# jms578.net
KiCad netlist of a schematic drawn in Altium Designer
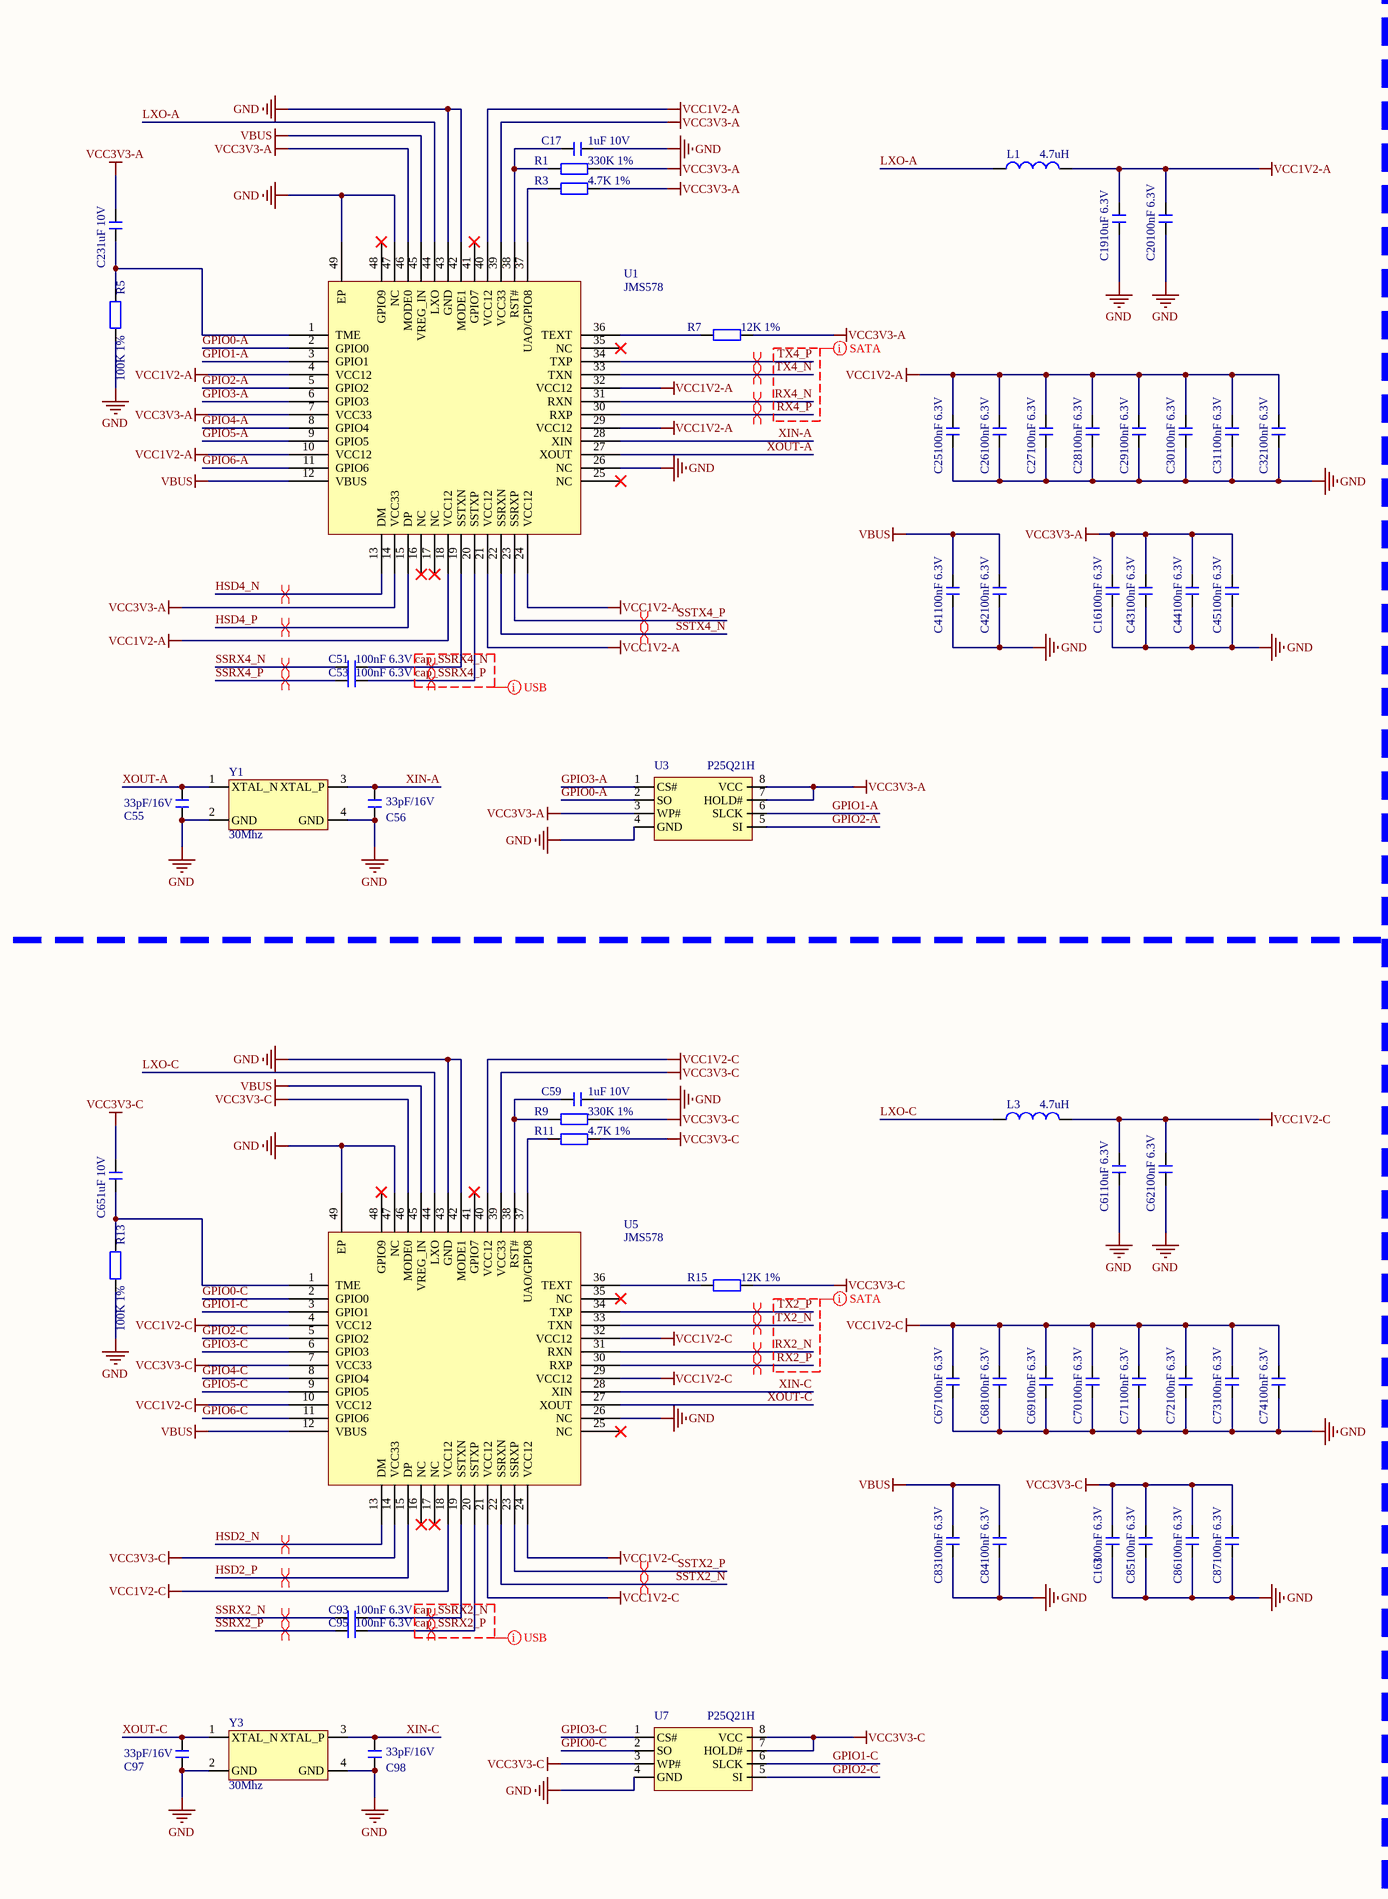
[diagram p0: jms578.SchDoc, left]
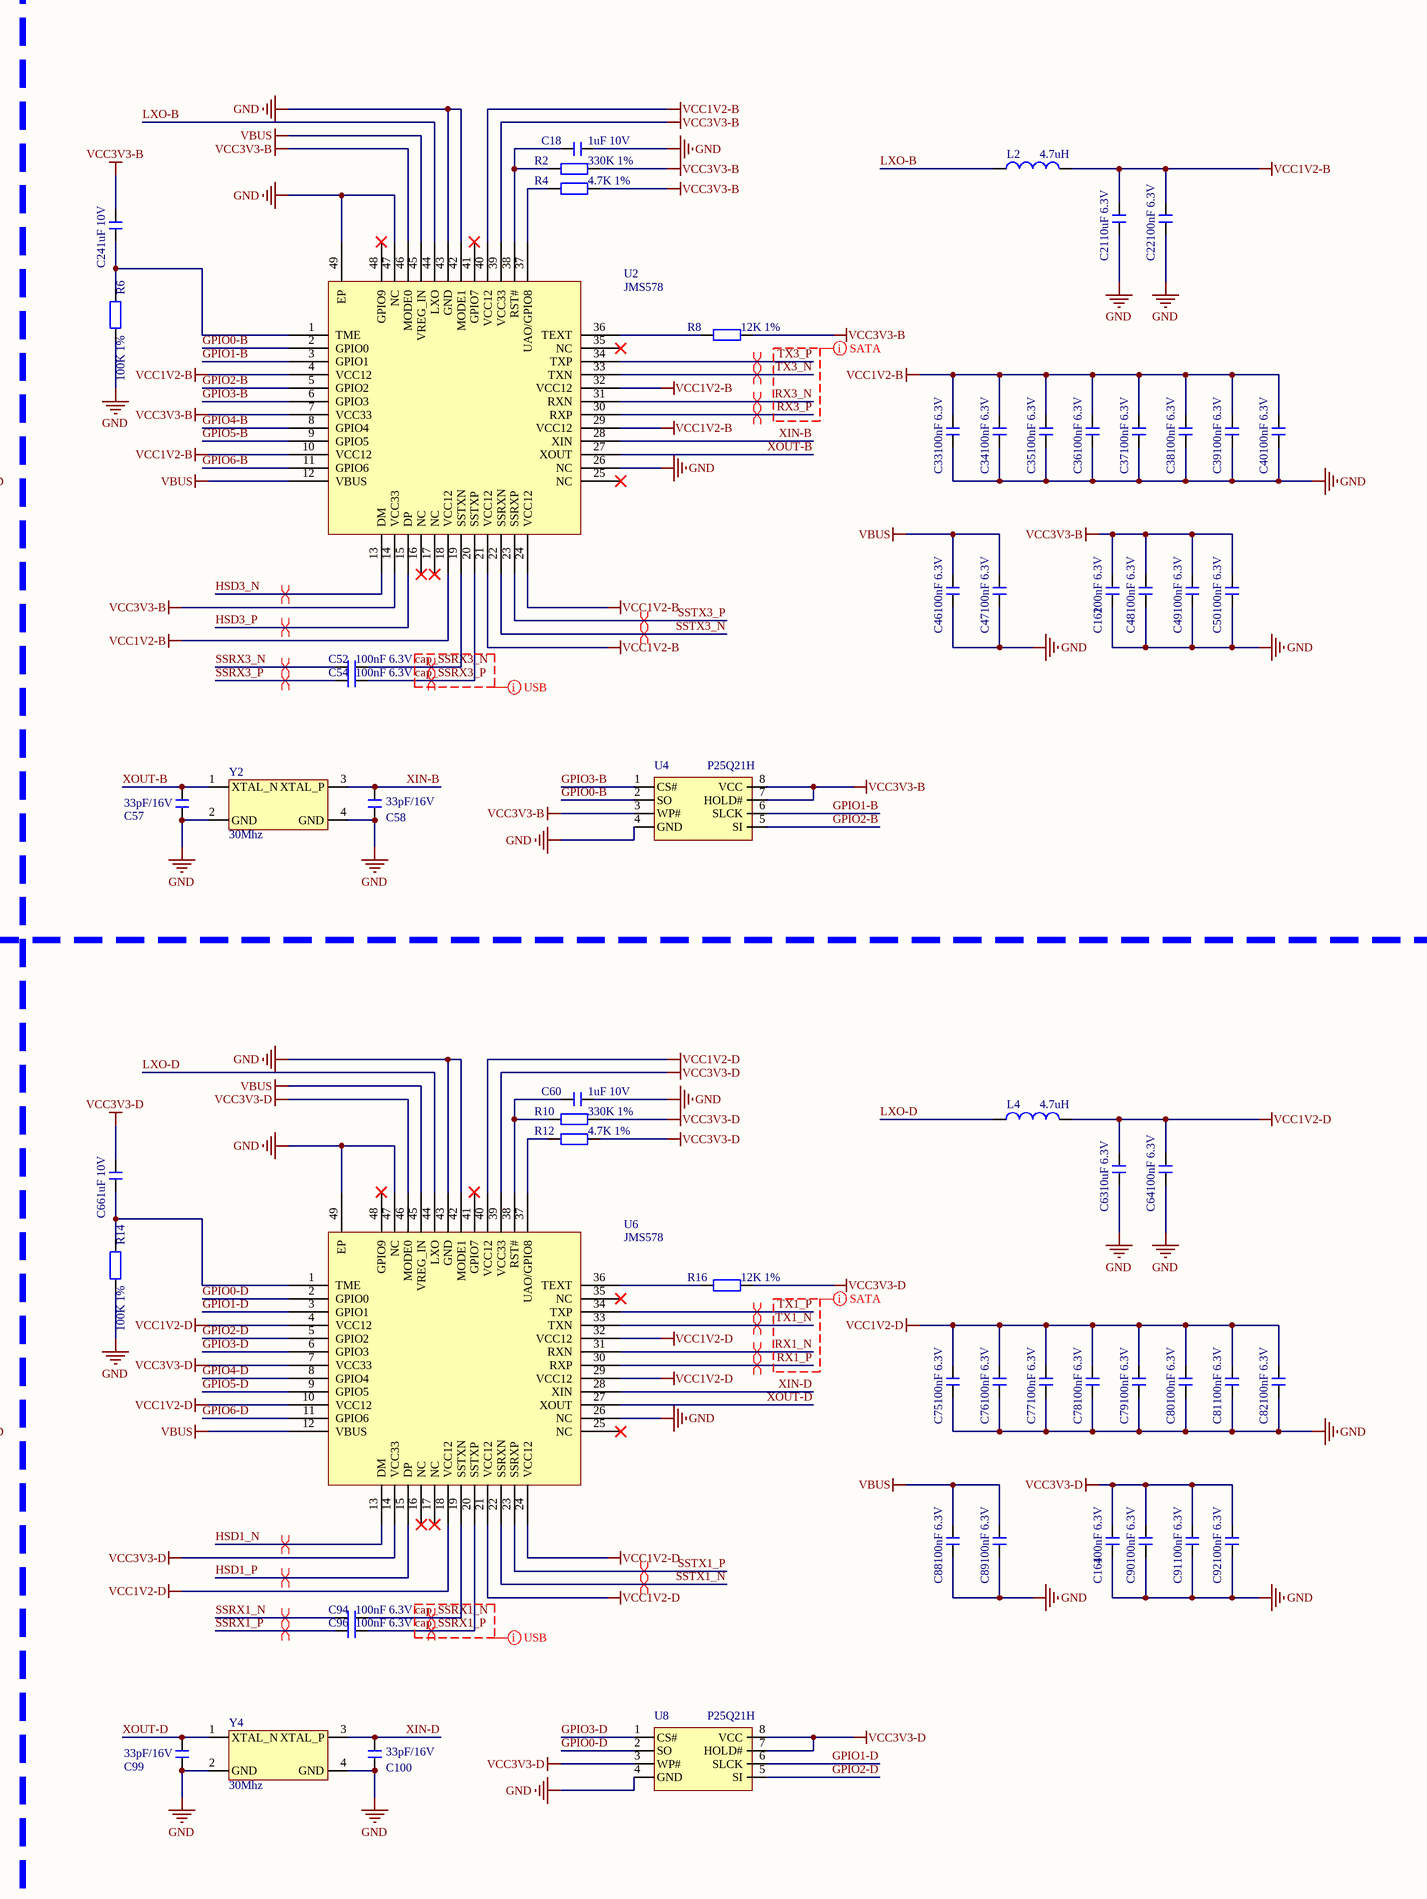
[diagram p1: jms578.SchDoc, right]

(export (version "E")
  (design (tool "Eeschema 10.0.6"))
  (components
    (comp (ref "C17")
      (value "1uF 10V")
      (footprint "C0402_L")
      (description "无极性贴片电容")
      (fields (field (name "版权归属") "源创客"))
      (libsource (lib "Capacitor") (part "C"))
    )
    (comp (ref "C18")
      (value "1uF 10V")
      (footprint "C0402_L")
      (description "无极性贴片电容")
      (fields (field (name "版权归属") "源创客"))
      (libsource (lib "Capacitor") (part "C"))
    )
    (comp (ref "C19")
      (value "10uF 6.3V")
      (footprint "C0603_L")
      (description "无极性贴片电容")
      (fields (field (name "版权归属") "源创客"))
      (libsource (lib "Capacitor") (part "C"))
    )
    (comp (ref "C20")
      (value "100nF 6.3V")
      (footprint "C0402_L")
      (description "无极性贴片电容")
      (fields (field (name "版权归属") "源创客"))
      (libsource (lib "Capacitor") (part "C"))
    )
    (comp (ref "C21")
      (value "10uF 6.3V")
      (footprint "C0603_L")
      (description "无极性贴片电容")
      (fields (field (name "版权归属") "源创客"))
      (libsource (lib "Capacitor") (part "C"))
    )
    (comp (ref "C22")
      (value "100nF 6.3V")
      (footprint "C0402_L")
      (description "无极性贴片电容")
      (fields (field (name "版权归属") "源创客"))
      (libsource (lib "Capacitor") (part "C"))
    )
    (comp (ref "C23")
      (value "1uF 10V")
      (footprint "C0402_L")
      (description "无极性贴片电容")
      (fields (field (name "版权归属") "源创客"))
      (libsource (lib "Capacitor") (part "C"))
    )
    (comp (ref "C24")
      (value "1uF 10V")
      (footprint "C0402_L")
      (description "无极性贴片电容")
      (fields (field (name "版权归属") "源创客"))
      (libsource (lib "Capacitor") (part "C"))
    )
    (comp (ref "C25")
      (value "100nF 6.3V")
      (footprint "C0402_L")
      (description "无极性贴片电容")
      (fields (field (name "版权归属") "源创客"))
      (libsource (lib "Capacitor") (part "C"))
    )
    (comp (ref "C26")
      (value "100nF 6.3V")
      (footprint "C0402_L")
      (description "无极性贴片电容")
      (fields (field (name "版权归属") "源创客"))
      (libsource (lib "Capacitor") (part "C"))
    )
    (comp (ref "C27")
      (value "100nF 6.3V")
      (footprint "C0402_L")
      (description "无极性贴片电容")
      (fields (field (name "版权归属") "源创客"))
      (libsource (lib "Capacitor") (part "C"))
    )
    (comp (ref "C28")
      (value "100nF 6.3V")
      (footprint "C0402_L")
      (description "无极性贴片电容")
      (fields (field (name "版权归属") "源创客"))
      (libsource (lib "Capacitor") (part "C"))
    )
    (comp (ref "C29")
      (value "100nF 6.3V")
      (footprint "C0402_L")
      (description "无极性贴片电容")
      (fields (field (name "版权归属") "源创客"))
      (libsource (lib "Capacitor") (part "C"))
    )
    (comp (ref "C30")
      (value "100nF 6.3V")
      (footprint "C0402_L")
      (description "无极性贴片电容")
      (fields (field (name "版权归属") "源创客"))
      (libsource (lib "Capacitor") (part "C"))
    )
    (comp (ref "C31")
      (value "100nF 6.3V")
      (footprint "C0402_L")
      (description "无极性贴片电容")
      (fields (field (name "版权归属") "源创客"))
      (libsource (lib "Capacitor") (part "C"))
    )
    (comp (ref "C32")
      (value "100nF 6.3V")
      (footprint "C0402_L")
      (description "无极性贴片电容")
      (fields (field (name "版权归属") "源创客"))
      (libsource (lib "Capacitor") (part "C"))
    )
    (comp (ref "C33")
      (value "100nF 6.3V")
      (footprint "C0402_L")
      (description "无极性贴片电容")
      (fields (field (name "版权归属") "源创客"))
      (libsource (lib "Capacitor") (part "C"))
    )
    (comp (ref "C34")
      (value "100nF 6.3V")
      (footprint "C0402_L")
      (description "无极性贴片电容")
      (fields (field (name "版权归属") "源创客"))
      (libsource (lib "Capacitor") (part "C"))
    )
    (comp (ref "C35")
      (value "100nF 6.3V")
      (footprint "C0402_L")
      (description "无极性贴片电容")
      (fields (field (name "版权归属") "源创客"))
      (libsource (lib "Capacitor") (part "C"))
    )
    (comp (ref "C36")
      (value "100nF 6.3V")
      (footprint "C0402_L")
      (description "无极性贴片电容")
      (fields (field (name "版权归属") "源创客"))
      (libsource (lib "Capacitor") (part "C"))
    )
    (comp (ref "C37")
      (value "100nF 6.3V")
      (footprint "C0402_L")
      (description "无极性贴片电容")
      (fields (field (name "版权归属") "源创客"))
      (libsource (lib "Capacitor") (part "C"))
    )
    (comp (ref "C38")
      (value "100nF 6.3V")
      (footprint "C0402_L")
      (description "无极性贴片电容")
      (fields (field (name "版权归属") "源创客"))
      (libsource (lib "Capacitor") (part "C"))
    )
    (comp (ref "C39")
      (value "100nF 6.3V")
      (footprint "C0402_L")
      (description "无极性贴片电容")
      (fields (field (name "版权归属") "源创客"))
      (libsource (lib "Capacitor") (part "C"))
    )
    (comp (ref "C40")
      (value "100nF 6.3V")
      (footprint "C0402_L")
      (description "无极性贴片电容")
      (fields (field (name "版权归属") "源创客"))
      (libsource (lib "Capacitor") (part "C"))
    )
    (comp (ref "C41")
      (value "100nF 6.3V")
      (footprint "C0402_L")
      (description "无极性贴片电容")
      (fields (field (name "版权归属") "源创客"))
      (libsource (lib "Capacitor") (part "C"))
    )
    (comp (ref "C42")
      (value "100nF 6.3V")
      (footprint "C0402_L")
      (description "无极性贴片电容")
      (fields (field (name "版权归属") "源创客"))
      (libsource (lib "Capacitor") (part "C"))
    )
    (comp (ref "C43")
      (value "100nF 6.3V")
      (footprint "C0402_L")
      (description "无极性贴片电容")
      (fields (field (name "版权归属") "源创客"))
      (libsource (lib "Capacitor") (part "C"))
    )
    (comp (ref "C44")
      (value "100nF 6.3V")
      (footprint "C0402_L")
      (description "无极性贴片电容")
      (fields (field (name "版权归属") "源创客"))
      (libsource (lib "Capacitor") (part "C"))
    )
    (comp (ref "C45")
      (value "100nF 6.3V")
      (footprint "C0402_L")
      (description "无极性贴片电容")
      (fields (field (name "版权归属") "源创客"))
      (libsource (lib "Capacitor") (part "C"))
    )
    (comp (ref "C46")
      (value "100nF 6.3V")
      (footprint "C0402_L")
      (description "无极性贴片电容")
      (fields (field (name "版权归属") "源创客"))
      (libsource (lib "Capacitor") (part "C"))
    )
    (comp (ref "C47")
      (value "100nF 6.3V")
      (footprint "C0402_L")
      (description "无极性贴片电容")
      (fields (field (name "版权归属") "源创客"))
      (libsource (lib "Capacitor") (part "C"))
    )
    (comp (ref "C48")
      (value "100nF 6.3V")
      (footprint "C0402_L")
      (description "无极性贴片电容")
      (fields (field (name "版权归属") "源创客"))
      (libsource (lib "Capacitor") (part "C"))
    )
    (comp (ref "C49")
      (value "100nF 6.3V")
      (footprint "C0402_L")
      (description "无极性贴片电容")
      (fields (field (name "版权归属") "源创客"))
      (libsource (lib "Capacitor") (part "C"))
    )
    (comp (ref "C50")
      (value "100nF 6.3V")
      (footprint "C0402_L")
      (description "无极性贴片电容")
      (fields (field (name "版权归属") "源创客"))
      (libsource (lib "Capacitor") (part "C"))
    )
    (comp (ref "C51")
      (value "100nF 6.3V")
      (footprint "C0402_L")
      (description "无极性贴片电容")
      (fields (field (name "版权归属") "源创客"))
      (libsource (lib "Capacitor") (part "C"))
    )
    (comp (ref "C52")
      (value "100nF 6.3V")
      (footprint "C0402_L")
      (description "无极性贴片电容")
      (fields (field (name "版权归属") "源创客"))
      (libsource (lib "Capacitor") (part "C"))
    )
    (comp (ref "C53")
      (value "100nF 6.3V")
      (footprint "C0402_L")
      (description "无极性贴片电容")
      (fields (field (name "版权归属") "源创客"))
      (libsource (lib "Capacitor") (part "C"))
    )
    (comp (ref "C54")
      (value "100nF 6.3V")
      (footprint "C0402_L")
      (description "无极性贴片电容")
      (fields (field (name "版权归属") "源创客"))
      (libsource (lib "Capacitor") (part "C"))
    )
    (comp (ref "C55")
      (value "33pF/16V")
      (footprint "C0402_L")
      (description "无极性贴片电容")
      (fields (field (name "版权归属") "源创客"))
      (libsource (lib "Capacitor") (part "C"))
    )
    (comp (ref "C56")
      (value "33pF/16V")
      (footprint "C0402_L")
      (description "无极性贴片电容")
      (fields (field (name "版权归属") "源创客"))
      (libsource (lib "Capacitor") (part "C"))
    )
    (comp (ref "C57")
      (value "33pF/16V")
      (footprint "C0402_L")
      (description "无极性贴片电容")
      (fields (field (name "版权归属") "源创客"))
      (libsource (lib "Capacitor") (part "C"))
    )
    (comp (ref "C58")
      (value "33pF/16V")
      (footprint "C0402_L")
      (description "无极性贴片电容")
      (fields (field (name "版权归属") "源创客"))
      (libsource (lib "Capacitor") (part "C"))
    )
    (comp (ref "C59")
      (value "1uF 10V")
      (footprint "C0402_L")
      (description "无极性贴片电容")
      (fields (field (name "版权归属") "源创客"))
      (libsource (lib "Capacitor") (part "C"))
    )
    (comp (ref "C60")
      (value "1uF 10V")
      (footprint "C0402_L")
      (description "无极性贴片电容")
      (fields (field (name "版权归属") "源创客"))
      (libsource (lib "Capacitor") (part "C"))
    )
    (comp (ref "C61")
      (value "10uF 6.3V")
      (footprint "C0603_L")
      (description "无极性贴片电容")
      (fields (field (name "版权归属") "源创客"))
      (libsource (lib "Capacitor") (part "C"))
    )
    (comp (ref "C62")
      (value "100nF 6.3V")
      (footprint "C0402_L")
      (description "无极性贴片电容")
      (fields (field (name "版权归属") "源创客"))
      (libsource (lib "Capacitor") (part "C"))
    )
    (comp (ref "C63")
      (value "10uF 6.3V")
      (footprint "C0603_L")
      (description "无极性贴片电容")
      (fields (field (name "版权归属") "源创客"))
      (libsource (lib "Capacitor") (part "C"))
    )
    (comp (ref "C64")
      (value "100nF 6.3V")
      (footprint "C0402_L")
      (description "无极性贴片电容")
      (fields (field (name "版权归属") "源创客"))
      (libsource (lib "Capacitor") (part "C"))
    )
    (comp (ref "C65")
      (value "1uF 10V")
      (footprint "C0402_L")
      (description "无极性贴片电容")
      (fields (field (name "版权归属") "源创客"))
      (libsource (lib "Capacitor") (part "C"))
    )
    (comp (ref "C66")
      (value "1uF 10V")
      (footprint "C0402_L")
      (description "无极性贴片电容")
      (fields (field (name "版权归属") "源创客"))
      (libsource (lib "Capacitor") (part "C"))
    )
    (comp (ref "C67")
      (value "100nF 6.3V")
      (footprint "C0402_L")
      (description "无极性贴片电容")
      (fields (field (name "版权归属") "源创客"))
      (libsource (lib "Capacitor") (part "C"))
    )
    (comp (ref "C68")
      (value "100nF 6.3V")
      (footprint "C0402_L")
      (description "无极性贴片电容")
      (fields (field (name "版权归属") "源创客"))
      (libsource (lib "Capacitor") (part "C"))
    )
    (comp (ref "C69")
      (value "100nF 6.3V")
      (footprint "C0402_L")
      (description "无极性贴片电容")
      (fields (field (name "版权归属") "源创客"))
      (libsource (lib "Capacitor") (part "C"))
    )
    (comp (ref "C70")
      (value "100nF 6.3V")
      (footprint "C0402_L")
      (description "无极性贴片电容")
      (fields (field (name "版权归属") "源创客"))
      (libsource (lib "Capacitor") (part "C"))
    )
    (comp (ref "C71")
      (value "100nF 6.3V")
      (footprint "C0402_L")
      (description "无极性贴片电容")
      (fields (field (name "版权归属") "源创客"))
      (libsource (lib "Capacitor") (part "C"))
    )
    (comp (ref "C72")
      (value "100nF 6.3V")
      (footprint "C0402_L")
      (description "无极性贴片电容")
      (fields (field (name "版权归属") "源创客"))
      (libsource (lib "Capacitor") (part "C"))
    )
    (comp (ref "C73")
      (value "100nF 6.3V")
      (footprint "C0402_L")
      (description "无极性贴片电容")
      (fields (field (name "版权归属") "源创客"))
      (libsource (lib "Capacitor") (part "C"))
    )
    (comp (ref "C74")
      (value "100nF 6.3V")
      (footprint "C0402_L")
      (description "无极性贴片电容")
      (fields (field (name "版权归属") "源创客"))
      (libsource (lib "Capacitor") (part "C"))
    )
    (comp (ref "C75")
      (value "100nF 6.3V")
      (footprint "C0402_L")
      (description "无极性贴片电容")
      (fields (field (name "版权归属") "源创客"))
      (libsource (lib "Capacitor") (part "C"))
    )
    (comp (ref "C76")
      (value "100nF 6.3V")
      (footprint "C0402_L")
      (description "无极性贴片电容")
      (fields (field (name "版权归属") "源创客"))
      (libsource (lib "Capacitor") (part "C"))
    )
    (comp (ref "C77")
      (value "100nF 6.3V")
      (footprint "C0402_L")
      (description "无极性贴片电容")
      (fields (field (name "版权归属") "源创客"))
      (libsource (lib "Capacitor") (part "C"))
    )
    (comp (ref "C78")
      (value "100nF 6.3V")
      (footprint "C0402_L")
      (description "无极性贴片电容")
      (fields (field (name "版权归属") "源创客"))
      (libsource (lib "Capacitor") (part "C"))
    )
    (comp (ref "C79")
      (value "100nF 6.3V")
      (footprint "C0402_L")
      (description "无极性贴片电容")
      (fields (field (name "版权归属") "源创客"))
      (libsource (lib "Capacitor") (part "C"))
    )
    (comp (ref "C80")
      (value "100nF 6.3V")
      (footprint "C0402_L")
      (description "无极性贴片电容")
      (fields (field (name "版权归属") "源创客"))
      (libsource (lib "Capacitor") (part "C"))
    )
    (comp (ref "C81")
      (value "100nF 6.3V")
      (footprint "C0402_L")
      (description "无极性贴片电容")
      (fields (field (name "版权归属") "源创客"))
      (libsource (lib "Capacitor") (part "C"))
    )
    (comp (ref "C82")
      (value "100nF 6.3V")
      (footprint "C0402_L")
      (description "无极性贴片电容")
      (fields (field (name "版权归属") "源创客"))
      (libsource (lib "Capacitor") (part "C"))
    )
    (comp (ref "C83")
      (value "100nF 6.3V")
      (footprint "C0402_L")
      (description "无极性贴片电容")
      (fields (field (name "版权归属") "源创客"))
      (libsource (lib "Capacitor") (part "C"))
    )
    (comp (ref "C84")
      (value "100nF 6.3V")
      (footprint "C0402_L")
      (description "无极性贴片电容")
      (fields (field (name "版权归属") "源创客"))
      (libsource (lib "Capacitor") (part "C"))
    )
    (comp (ref "C85")
      (value "100nF 6.3V")
      (footprint "C0402_L")
      (description "无极性贴片电容")
      (fields (field (name "版权归属") "源创客"))
      (libsource (lib "Capacitor") (part "C"))
    )
    (comp (ref "C86")
      (value "100nF 6.3V")
      (footprint "C0402_L")
      (description "无极性贴片电容")
      (fields (field (name "版权归属") "源创客"))
      (libsource (lib "Capacitor") (part "C"))
    )
    (comp (ref "C87")
      (value "100nF 6.3V")
      (footprint "C0402_L")
      (description "无极性贴片电容")
      (fields (field (name "版权归属") "源创客"))
      (libsource (lib "Capacitor") (part "C"))
    )
    (comp (ref "C88")
      (value "100nF 6.3V")
      (footprint "C0402_L")
      (description "无极性贴片电容")
      (fields (field (name "版权归属") "源创客"))
      (libsource (lib "Capacitor") (part "C"))
    )
    (comp (ref "C89")
      (value "100nF 6.3V")
      (footprint "C0402_L")
      (description "无极性贴片电容")
      (fields (field (name "版权归属") "源创客"))
      (libsource (lib "Capacitor") (part "C"))
    )
    (comp (ref "C90")
      (value "100nF 6.3V")
      (footprint "C0402_L")
      (description "无极性贴片电容")
      (fields (field (name "版权归属") "源创客"))
      (libsource (lib "Capacitor") (part "C"))
    )
    (comp (ref "C91")
      (value "100nF 6.3V")
      (footprint "C0402_L")
      (description "无极性贴片电容")
      (fields (field (name "版权归属") "源创客"))
      (libsource (lib "Capacitor") (part "C"))
    )
    (comp (ref "C92")
      (value "100nF 6.3V")
      (footprint "C0402_L")
      (description "无极性贴片电容")
      (fields (field (name "版权归属") "源创客"))
      (libsource (lib "Capacitor") (part "C"))
    )
    (comp (ref "C93")
      (value "100nF 6.3V")
      (footprint "C0402_L")
      (description "无极性贴片电容")
      (fields (field (name "版权归属") "源创客"))
      (libsource (lib "Capacitor") (part "C"))
    )
    (comp (ref "C94")
      (value "100nF 6.3V")
      (footprint "C0402_L")
      (description "无极性贴片电容")
      (fields (field (name "版权归属") "源创客"))
      (libsource (lib "Capacitor") (part "C"))
    )
    (comp (ref "C95")
      (value "100nF 6.3V")
      (footprint "C0402_L")
      (description "无极性贴片电容")
      (fields (field (name "版权归属") "源创客"))
      (libsource (lib "Capacitor") (part "C"))
    )
    (comp (ref "C96")
      (value "100nF 6.3V")
      (footprint "C0402_L")
      (description "无极性贴片电容")
      (fields (field (name "版权归属") "源创客"))
      (libsource (lib "Capacitor") (part "C"))
    )
    (comp (ref "C97")
      (value "33pF/16V")
      (footprint "C0402_L")
      (description "无极性贴片电容")
      (fields (field (name "版权归属") "源创客"))
      (libsource (lib "Capacitor") (part "C"))
    )
    (comp (ref "C98")
      (value "33pF/16V")
      (footprint "C0402_L")
      (description "无极性贴片电容")
      (fields (field (name "版权归属") "源创客"))
      (libsource (lib "Capacitor") (part "C"))
    )
    (comp (ref "C99")
      (value "33pF/16V")
      (footprint "C0402_L")
      (description "无极性贴片电容")
      (fields (field (name "版权归属") "源创客"))
      (libsource (lib "Capacitor") (part "C"))
    )
    (comp (ref "C100")
      (value "33pF/16V")
      (footprint "C0402_L")
      (description "无极性贴片电容")
      (fields (field (name "版权归属") "源创客"))
      (libsource (lib "Capacitor") (part "C"))
    )
    (comp (ref "C161")
      (value "100nF 6.3V")
      (footprint "C0402_L")
      (description "无极性贴片电容")
      (fields (field (name "版权归属") "源创客"))
      (libsource (lib "Capacitor") (part "C"))
    )
    (comp (ref "C162")
      (value "100nF 6.3V")
      (footprint "C0402_L")
      (description "无极性贴片电容")
      (fields (field (name "版权归属") "源创客"))
      (libsource (lib "Capacitor") (part "C"))
    )
    (comp (ref "C163")
      (value "100nF 6.3V")
      (footprint "C0402_L")
      (description "无极性贴片电容")
      (fields (field (name "版权归属") "源创客"))
      (libsource (lib "Capacitor") (part "C"))
    )
    (comp (ref "C164")
      (value "100nF 6.3V")
      (footprint "C0402_L")
      (description "无极性贴片电容")
      (fields (field (name "版权归属") "源创客"))
      (libsource (lib "Capacitor") (part "C"))
    )
    (comp (ref "L1")
      (value "4.7uH")
      (footprint "NR2520")
      (description "小功率贴片电感")
      (fields (field (name "版权归属") "源创客"))
      (libsource (lib "Inductor") (part "L"))
    )
    (comp (ref "L2")
      (value "4.7uH")
      (footprint "NR2520")
      (description "小功率贴片电感")
      (fields (field (name "版权归属") "源创客"))
      (libsource (lib "Inductor") (part "L"))
    )
    (comp (ref "L3")
      (value "4.7uH")
      (footprint "NR2520")
      (description "小功率贴片电感")
      (fields (field (name "版权归属") "源创客"))
      (libsource (lib "Inductor") (part "L"))
    )
    (comp (ref "L4")
      (value "4.7uH")
      (footprint "NR2520")
      (description "小功率贴片电感")
      (fields (field (name "版权归属") "源创客"))
      (libsource (lib "Inductor") (part "L"))
    )
    (comp (ref "R1")
      (value "330K 1%")
      (footprint "R0402_L")
      (description "贴片电阻")
      (fields (field (name "版权归属") "源创客"))
      (libsource (lib "Resistor") (part "R"))
    )
    (comp (ref "R2")
      (value "330K 1%")
      (footprint "R0402_L")
      (description "贴片电阻")
      (fields (field (name "版权归属") "源创客"))
      (libsource (lib "Resistor") (part "R"))
    )
    (comp (ref "R3")
      (value "4.7K 1%")
      (footprint "R0402_L")
      (description "贴片电阻")
      (fields (field (name "版权归属") "源创客"))
      (libsource (lib "Resistor") (part "R"))
    )
    (comp (ref "R4")
      (value "4.7K 1%")
      (footprint "R0402_L")
      (description "贴片电阻")
      (fields (field (name "版权归属") "源创客"))
      (libsource (lib "Resistor") (part "R"))
    )
    (comp (ref "R5")
      (value "100K 1%")
      (footprint "R0402_L")
      (description "贴片电阻")
      (fields (field (name "版权归属") "源创客"))
      (libsource (lib "Resistor") (part "R"))
    )
    (comp (ref "R6")
      (value "100K 1%")
      (footprint "R0402_L")
      (description "贴片电阻")
      (fields (field (name "版权归属") "源创客"))
      (libsource (lib "Resistor") (part "R"))
    )
    (comp (ref "R7")
      (value "12K 1%")
      (footprint "R0402_L")
      (description "贴片电阻")
      (fields (field (name "版权归属") "源创客"))
      (libsource (lib "Resistor") (part "R"))
    )
    (comp (ref "R8")
      (value "12K 1%")
      (footprint "R0402_L")
      (description "贴片电阻")
      (fields (field (name "版权归属") "源创客"))
      (libsource (lib "Resistor") (part "R"))
    )
    (comp (ref "R9")
      (value "330K 1%")
      (footprint "R0402_L")
      (description "贴片电阻")
      (fields (field (name "版权归属") "源创客"))
      (libsource (lib "Resistor") (part "R"))
    )
    (comp (ref "R10")
      (value "330K 1%")
      (footprint "R0402_L")
      (description "贴片电阻")
      (fields (field (name "版权归属") "源创客"))
      (libsource (lib "Resistor") (part "R"))
    )
    (comp (ref "R11")
      (value "4.7K 1%")
      (footprint "R0402_L")
      (description "贴片电阻")
      (fields (field (name "版权归属") "源创客"))
      (libsource (lib "Resistor") (part "R"))
    )
    (comp (ref "R12")
      (value "4.7K 1%")
      (footprint "R0402_L")
      (description "贴片电阻")
      (fields (field (name "版权归属") "源创客"))
      (libsource (lib "Resistor") (part "R"))
    )
    (comp (ref "R13")
      (value "100K 1%")
      (footprint "R0402_L")
      (description "贴片电阻")
      (fields (field (name "版权归属") "源创客"))
      (libsource (lib "Resistor") (part "R"))
    )
    (comp (ref "R14")
      (value "100K 1%")
      (footprint "R0402_L")
      (description "贴片电阻")
      (fields (field (name "版权归属") "源创客"))
      (libsource (lib "Resistor") (part "R"))
    )
    (comp (ref "R15")
      (value "12K 1%")
      (footprint "R0402_L")
      (description "贴片电阻")
      (fields (field (name "版权归属") "源创客"))
      (libsource (lib "Resistor") (part "R"))
    )
    (comp (ref "R16")
      (value "12K 1%")
      (footprint "R0402_L")
      (description "贴片电阻")
      (fields (field (name "版权归属") "源创客"))
      (libsource (lib "Resistor") (part "R"))
    )
    (comp (ref "U1")
      (value "JMS578")
      (footprint "QFN48-L6.0-W6.0-P0.4")
      (libsource (lib "Brage") (part "JMS578"))
    )
    (comp (ref "U2")
      (value "JMS578")
      (footprint "QFN48-L6.0-W6.0-P0.4")
      (libsource (lib "Brage") (part "JMS578"))
    )
    (comp (ref "U3") (value "P25Q21H") (footprint "SOP8_L") (libsource (lib "Flash") (part "P25D40H")))
    (comp (ref "U4") (value "P25Q21H") (footprint "SOP8_L") (libsource (lib "Flash") (part "P25D40H")))
    (comp (ref "U5")
      (value "JMS578")
      (footprint "QFN48-L6.0-W6.0-P0.4")
      (libsource (lib "Brage") (part "JMS578"))
    )
    (comp (ref "U6")
      (value "JMS578")
      (footprint "QFN48-L6.0-W6.0-P0.4")
      (libsource (lib "Brage") (part "JMS578"))
    )
    (comp (ref "U7") (value "P25Q21H") (footprint "SOP8_L") (libsource (lib "Flash") (part "P25D40H")))
    (comp (ref "U8") (value "P25Q21H") (footprint "SOP8_L") (libsource (lib "Flash") (part "P25D40H")))
    (comp (ref "Y1") (value "30Mhz") (footprint "OSC 3225-4P") (libsource (lib "Crystal") (part "Crystal")))
    (comp (ref "Y2") (value "30Mhz") (footprint "OSC 3225-4P") (libsource (lib "Crystal") (part "Crystal")))
    (comp (ref "Y3") (value "30Mhz") (footprint "OSC 3225-4P") (libsource (lib "Crystal") (part "Crystal")))
    (comp (ref "Y4") (value "30Mhz") (footprint "OSC 3225-4P") (libsource (lib "Crystal") (part "Crystal")))
  )
  (nets
    (net (code "1") (name "/GPIO0-A") (class "Default")
      (node (ref "U1") (pin "2") (pinfunction "GPIO0_2") (pintype "passive"))
      (node (ref "U3") (pin "2") (pinfunction "SO_2") (pintype "passive"))
    )
    (net (code "2") (name "/GPIO0-B") (class "Default")
      (node (ref "U2") (pin "2") (pinfunction "GPIO0_2") (pintype "passive"))
      (node (ref "U4") (pin "2") (pinfunction "SO_2") (pintype "passive"))
    )
    (net (code "3") (name "/GPIO0-C") (class "Default")
      (node (ref "U5") (pin "2") (pinfunction "GPIO0_2") (pintype "passive"))
      (node (ref "U7") (pin "2") (pinfunction "SO_2") (pintype "passive"))
    )
    (net (code "4") (name "/GPIO0-D") (class "Default")
      (node (ref "U6") (pin "2") (pinfunction "GPIO0_2") (pintype "passive"))
      (node (ref "U8") (pin "2") (pinfunction "SO_2") (pintype "passive"))
    )
    (net (code "5") (name "/GPIO1-A") (class "Default")
      (node (ref "U1") (pin "3") (pinfunction "GPIO1_3") (pintype "passive"))
      (node (ref "U3") (pin "6") (pinfunction "SLCK_6") (pintype "passive"))
    )
    (net (code "6") (name "/GPIO1-B") (class "Default")
      (node (ref "U2") (pin "3") (pinfunction "GPIO1_3") (pintype "passive"))
      (node (ref "U4") (pin "6") (pinfunction "SLCK_6") (pintype "passive"))
    )
    (net (code "7") (name "/GPIO1-C") (class "Default")
      (node (ref "U5") (pin "3") (pinfunction "GPIO1_3") (pintype "passive"))
      (node (ref "U7") (pin "6") (pinfunction "SLCK_6") (pintype "passive"))
    )
    (net (code "8") (name "/GPIO1-D") (class "Default")
      (node (ref "U6") (pin "3") (pinfunction "GPIO1_3") (pintype "passive"))
      (node (ref "U8") (pin "6") (pinfunction "SLCK_6") (pintype "passive"))
    )
    (net (code "9") (name "/GPIO2-A") (class "Default")
      (node (ref "U1") (pin "5") (pinfunction "GPIO2_5") (pintype "passive"))
      (node (ref "U3") (pin "5") (pinfunction "SI_5") (pintype "passive"))
    )
    (net (code "10") (name "/GPIO2-B") (class "Default")
      (node (ref "U2") (pin "5") (pinfunction "GPIO2_5") (pintype "passive"))
      (node (ref "U4") (pin "5") (pinfunction "SI_5") (pintype "passive"))
    )
    (net (code "11") (name "/GPIO2-C") (class "Default")
      (node (ref "U5") (pin "5") (pinfunction "GPIO2_5") (pintype "passive"))
      (node (ref "U7") (pin "5") (pinfunction "SI_5") (pintype "passive"))
    )
    (net (code "12") (name "/GPIO2-D") (class "Default")
      (node (ref "U6") (pin "5") (pinfunction "GPIO2_5") (pintype "passive"))
      (node (ref "U8") (pin "5") (pinfunction "SI_5") (pintype "passive"))
    )
    (net (code "13") (name "/GPIO3-A") (class "Default")
      (node (ref "U1") (pin "6") (pinfunction "GPIO3_6") (pintype "passive"))
      (node (ref "U3") (pin "1") (pinfunction "CS#_1") (pintype "passive"))
    )
    (net (code "14") (name "/GPIO3-B") (class "Default")
      (node (ref "U2") (pin "6") (pinfunction "GPIO3_6") (pintype "passive"))
      (node (ref "U4") (pin "1") (pinfunction "CS#_1") (pintype "passive"))
    )
    (net (code "15") (name "/GPIO3-C") (class "Default")
      (node (ref "U5") (pin "6") (pinfunction "GPIO3_6") (pintype "passive"))
      (node (ref "U7") (pin "1") (pinfunction "CS#_1") (pintype "passive"))
    )
    (net (code "16") (name "/GPIO3-D") (class "Default")
      (node (ref "U6") (pin "6") (pinfunction "GPIO3_6") (pintype "passive"))
      (node (ref "U8") (pin "1") (pinfunction "CS#_1") (pintype "passive"))
    )
    (net (code "17") (name "/GPIO4-A") (class "Default")
      (node (ref "U1") (pin "8") (pinfunction "GPIO4_8") (pintype "passive"))
    )
    (net (code "18") (name "/GPIO4-B") (class "Default")
      (node (ref "U2") (pin "8") (pinfunction "GPIO4_8") (pintype "passive"))
    )
    (net (code "19") (name "/GPIO4-C") (class "Default")
      (node (ref "U5") (pin "8") (pinfunction "GPIO4_8") (pintype "passive"))
    )
    (net (code "20") (name "/GPIO4-D") (class "Default")
      (node (ref "U6") (pin "8") (pinfunction "GPIO4_8") (pintype "passive"))
    )
    (net (code "21") (name "/GPIO5-A") (class "Default")
      (node (ref "U1") (pin "9") (pinfunction "GPIO5_9") (pintype "passive"))
    )
    (net (code "22") (name "/GPIO5-B") (class "Default")
      (node (ref "U2") (pin "9") (pinfunction "GPIO5_9") (pintype "passive"))
    )
    (net (code "23") (name "/GPIO5-C") (class "Default")
      (node (ref "U5") (pin "9") (pinfunction "GPIO5_9") (pintype "passive"))
    )
    (net (code "24") (name "/GPIO5-D") (class "Default")
      (node (ref "U6") (pin "9") (pinfunction "GPIO5_9") (pintype "passive"))
    )
    (net (code "25") (name "/GPIO6-A") (class "Default")
      (node (ref "U1") (pin "11") (pinfunction "GPIO6_11") (pintype "passive"))
    )
    (net (code "26") (name "/GPIO6-B") (class "Default")
      (node (ref "U2") (pin "11") (pinfunction "GPIO6_11") (pintype "passive"))
    )
    (net (code "27") (name "/GPIO6-C") (class "Default")
      (node (ref "U5") (pin "11") (pinfunction "GPIO6_11") (pintype "passive"))
    )
    (net (code "28") (name "/GPIO6-D") (class "Default")
      (node (ref "U6") (pin "11") (pinfunction "GPIO6_11") (pintype "passive"))
    )
    (net (code "29") (name "/HSD1_N") (class "Default")
      (node (ref "U6") (pin "13") (pinfunction "DM_13") (pintype "passive"))
    )
    (net (code "30") (name "/HSD1_P") (class "Default")
      (node (ref "U6") (pin "15") (pinfunction "DP_15") (pintype "passive"))
    )
    (net (code "31") (name "/HSD2_N") (class "Default")
      (node (ref "U5") (pin "13") (pinfunction "DM_13") (pintype "passive"))
    )
    (net (code "32") (name "/HSD2_P") (class "Default")
      (node (ref "U5") (pin "15") (pinfunction "DP_15") (pintype "passive"))
    )
    (net (code "33") (name "/HSD3_N") (class "Default")
      (node (ref "U2") (pin "13") (pinfunction "DM_13") (pintype "passive"))
    )
    (net (code "34") (name "/HSD3_P") (class "Default")
      (node (ref "U2") (pin "15") (pinfunction "DP_15") (pintype "passive"))
    )
    (net (code "35") (name "/HSD4_N") (class "Default")
      (node (ref "U1") (pin "13") (pinfunction "DM_13") (pintype "passive"))
    )
    (net (code "36") (name "/HSD4_P") (class "Default")
      (node (ref "U1") (pin "15") (pinfunction "DP_15") (pintype "passive"))
    )
    (net (code "37") (name "/LXO-A") (class "Default")
      (node (ref "L1") (pin "1") (pinfunction "1_1") (pintype "passive"))
      (node (ref "U1") (pin "44") (pinfunction "LXO_44") (pintype "passive"))
    )
    (net (code "38") (name "/LXO-B") (class "Default")
      (node (ref "L2") (pin "1") (pinfunction "1_1") (pintype "passive"))
      (node (ref "U2") (pin "44") (pinfunction "LXO_44") (pintype "passive"))
    )
    (net (code "39") (name "/LXO-C") (class "Default")
      (node (ref "L3") (pin "1") (pinfunction "1_1") (pintype "passive"))
      (node (ref "U5") (pin "44") (pinfunction "LXO_44") (pintype "passive"))
    )
    (net (code "40") (name "/LXO-D") (class "Default")
      (node (ref "L4") (pin "1") (pinfunction "1_1") (pintype "passive"))
      (node (ref "U6") (pin "44") (pinfunction "LXO_44") (pintype "passive"))
    )
    (net (code "41") (name "/RX1_N") (class "Default")
      (node (ref "U6") (pin "31") (pinfunction "RXN_31") (pintype "passive"))
    )
    (net (code "42") (name "/RX1_P") (class "Default")
      (node (ref "U6") (pin "30") (pinfunction "RXP_30") (pintype "passive"))
    )
    (net (code "43") (name "/RX2_N") (class "Default")
      (node (ref "U5") (pin "31") (pinfunction "RXN_31") (pintype "passive"))
    )
    (net (code "44") (name "/RX2_P") (class "Default")
      (node (ref "U5") (pin "30") (pinfunction "RXP_30") (pintype "passive"))
    )
    (net (code "45") (name "/RX3_N") (class "Default")
      (node (ref "U2") (pin "31") (pinfunction "RXN_31") (pintype "passive"))
    )
    (net (code "46") (name "/RX3_P") (class "Default")
      (node (ref "U2") (pin "30") (pinfunction "RXP_30") (pintype "passive"))
    )
    (net (code "47") (name "/RX4_N") (class "Default")
      (node (ref "U1") (pin "31") (pinfunction "RXN_31") (pintype "passive"))
    )
    (net (code "48") (name "/RX4_P") (class "Default")
      (node (ref "U1") (pin "30") (pinfunction "RXP_30") (pintype "passive"))
    )
    (net (code "49") (name "/SSRX1_N") (class "Default")
      (node (ref "C94") (pin "1") (pinfunction "1_1") (pintype "passive"))
    )
    (net (code "50") (name "/SSRX1_P") (class "Default")
      (node (ref "C96") (pin "1") (pinfunction "1_1") (pintype "passive"))
    )
    (net (code "51") (name "/SSRX2_N") (class "Default")
      (node (ref "C93") (pin "1") (pinfunction "1_1") (pintype "passive"))
    )
    (net (code "52") (name "/SSRX2_P") (class "Default")
      (node (ref "C95") (pin "1") (pinfunction "1_1") (pintype "passive"))
    )
    (net (code "53") (name "/SSRX3_N") (class "Default")
      (node (ref "C52") (pin "1") (pinfunction "1_1") (pintype "passive"))
    )
    (net (code "54") (name "/SSRX3_P") (class "Default")
      (node (ref "C54") (pin "1") (pinfunction "1_1") (pintype "passive"))
    )
    (net (code "55") (name "/SSRX4_N") (class "Default")
      (node (ref "C51") (pin "1") (pinfunction "1_1") (pintype "passive"))
    )
    (net (code "56") (name "/SSRX4_P") (class "Default")
      (node (ref "C53") (pin "1") (pinfunction "1_1") (pintype "passive"))
    )
    (net (code "57") (name "/SSTX1_N") (class "Default")
      (node (ref "U6") (pin "22") (pinfunction "SSRXN_22") (pintype "passive"))
    )
    (net (code "58") (name "/SSTX1_P") (class "Default")
      (node (ref "U6") (pin "23") (pinfunction "SSRXP_23") (pintype "passive"))
    )
    (net (code "59") (name "/SSTX2_N") (class "Default")
      (node (ref "U5") (pin "22") (pinfunction "SSRXN_22") (pintype "passive"))
    )
    (net (code "60") (name "/SSTX2_P") (class "Default")
      (node (ref "U5") (pin "23") (pinfunction "SSRXP_23") (pintype "passive"))
    )
    (net (code "61") (name "/SSTX3_N") (class "Default")
      (node (ref "U2") (pin "22") (pinfunction "SSRXN_22") (pintype "passive"))
    )
    (net (code "62") (name "/SSTX3_P") (class "Default")
      (node (ref "U2") (pin "23") (pinfunction "SSRXP_23") (pintype "passive"))
    )
    (net (code "63") (name "/SSTX4_N") (class "Default")
      (node (ref "U1") (pin "22") (pinfunction "SSRXN_22") (pintype "passive"))
    )
    (net (code "64") (name "/SSTX4_P") (class "Default")
      (node (ref "U1") (pin "23") (pinfunction "SSRXP_23") (pintype "passive"))
    )
    (net (code "65") (name "/TX1_N") (class "Default")
      (node (ref "U6") (pin "33") (pinfunction "TXN_33") (pintype "passive"))
    )
    (net (code "66") (name "/TX1_P") (class "Default")
      (node (ref "U6") (pin "34") (pinfunction "TXP_34") (pintype "passive"))
    )
    (net (code "67") (name "/TX2_N") (class "Default")
      (node (ref "U5") (pin "33") (pinfunction "TXN_33") (pintype "passive"))
    )
    (net (code "68") (name "/TX2_P") (class "Default")
      (node (ref "U5") (pin "34") (pinfunction "TXP_34") (pintype "passive"))
    )
    (net (code "69") (name "/TX3_N") (class "Default")
      (node (ref "U2") (pin "33") (pinfunction "TXN_33") (pintype "passive"))
    )
    (net (code "70") (name "/TX3_P") (class "Default")
      (node (ref "U2") (pin "34") (pinfunction "TXP_34") (pintype "passive"))
    )
    (net (code "71") (name "/TX4_N") (class "Default")
      (node (ref "U1") (pin "33") (pinfunction "TXN_33") (pintype "passive"))
    )
    (net (code "72") (name "/TX4_P") (class "Default")
      (node (ref "U1") (pin "34") (pinfunction "TXP_34") (pintype "passive"))
    )
    (net (code "73") (name "/XIN-A") (class "Default")
      (node (ref "C56") (pin "1") (pinfunction "1_1") (pintype "passive"))
      (node (ref "U1") (pin "28") (pinfunction "XIN_28") (pintype "passive"))
      (node (ref "Y1") (pin "3") (pinfunction "XTAL_P_3") (pintype "passive"))
    )
    (net (code "74") (name "/XIN-B") (class "Default")
      (node (ref "C58") (pin "1") (pinfunction "1_1") (pintype "passive"))
      (node (ref "U2") (pin "28") (pinfunction "XIN_28") (pintype "passive"))
      (node (ref "Y2") (pin "3") (pinfunction "XTAL_P_3") (pintype "passive"))
    )
    (net (code "75") (name "/XIN-C") (class "Default")
      (node (ref "C98") (pin "1") (pinfunction "1_1") (pintype "passive"))
      (node (ref "U5") (pin "28") (pinfunction "XIN_28") (pintype "passive"))
      (node (ref "Y3") (pin "3") (pinfunction "XTAL_P_3") (pintype "passive"))
    )
    (net (code "76") (name "/XIN-D") (class "Default")
      (node (ref "C100") (pin "1") (pinfunction "1_1") (pintype "passive"))
      (node (ref "U6") (pin "28") (pinfunction "XIN_28") (pintype "passive"))
      (node (ref "Y4") (pin "3") (pinfunction "XTAL_P_3") (pintype "passive"))
    )
    (net (code "77") (name "/XOUT-A") (class "Default")
      (node (ref "C55") (pin "1") (pinfunction "1_1") (pintype "passive"))
      (node (ref "U1") (pin "27") (pinfunction "XOUT_27") (pintype "passive"))
      (node (ref "Y1") (pin "1") (pinfunction "XTAL_N_1") (pintype "passive"))
    )
    (net (code "78") (name "/XOUT-B") (class "Default")
      (node (ref "C57") (pin "1") (pinfunction "1_1") (pintype "passive"))
      (node (ref "U2") (pin "27") (pinfunction "XOUT_27") (pintype "passive"))
      (node (ref "Y2") (pin "1") (pinfunction "XTAL_N_1") (pintype "passive"))
    )
    (net (code "79") (name "/XOUT-C") (class "Default")
      (node (ref "C97") (pin "1") (pinfunction "1_1") (pintype "passive"))
      (node (ref "U5") (pin "27") (pinfunction "XOUT_27") (pintype "passive"))
      (node (ref "Y3") (pin "1") (pinfunction "XTAL_N_1") (pintype "passive"))
    )
    (net (code "80") (name "/XOUT-D") (class "Default")
      (node (ref "C99") (pin "1") (pinfunction "1_1") (pintype "passive"))
      (node (ref "U6") (pin "27") (pinfunction "XOUT_27") (pintype "passive"))
      (node (ref "Y4") (pin "1") (pinfunction "XTAL_N_1") (pintype "passive"))
    )
    (net (code "81") (name "/cap_SSRX1_N") (class "Default")
      (node (ref "C94") (pin "2") (pinfunction "2_2") (pintype "passive"))
      (node (ref "U6") (pin "19") (pinfunction "SSTXN_19") (pintype "passive"))
    )
    (net (code "82") (name "/cap_SSRX1_P") (class "Default")
      (node (ref "C96") (pin "2") (pinfunction "2_2") (pintype "passive"))
      (node (ref "U6") (pin "20") (pinfunction "SSTXP_20") (pintype "passive"))
    )
    (net (code "83") (name "/cap_SSRX2_N") (class "Default")
      (node (ref "C93") (pin "2") (pinfunction "2_2") (pintype "passive"))
      (node (ref "U5") (pin "19") (pinfunction "SSTXN_19") (pintype "passive"))
    )
    (net (code "84") (name "/cap_SSRX2_P") (class "Default")
      (node (ref "C95") (pin "2") (pinfunction "2_2") (pintype "passive"))
      (node (ref "U5") (pin "20") (pinfunction "SSTXP_20") (pintype "passive"))
    )
    (net (code "85") (name "/cap_SSRX3_N") (class "Default")
      (node (ref "C52") (pin "2") (pinfunction "2_2") (pintype "passive"))
      (node (ref "U2") (pin "19") (pinfunction "SSTXN_19") (pintype "passive"))
    )
    (net (code "86") (name "/cap_SSRX3_P") (class "Default")
      (node (ref "C54") (pin "2") (pinfunction "2_2") (pintype "passive"))
      (node (ref "U2") (pin "20") (pinfunction "SSTXP_20") (pintype "passive"))
    )
    (net (code "87") (name "/cap_SSRX4_N") (class "Default")
      (node (ref "C51") (pin "2") (pinfunction "2_2") (pintype "passive"))
      (node (ref "U1") (pin "19") (pinfunction "SSTXN_19") (pintype "passive"))
    )
    (net (code "88") (name "/cap_SSRX4_P") (class "Default")
      (node (ref "C53") (pin "2") (pinfunction "2_2") (pintype "passive"))
      (node (ref "U1") (pin "20") (pinfunction "SSTXP_20") (pintype "passive"))
    )
    (net (code "89") (name "GND") (class "Default")
      (node (ref "C100") (pin "2") (pinfunction "2_2") (pintype "passive"))
      (node (ref "C161") (pin "1") (pinfunction "1_1") (pintype "passive"))
      (node (ref "C162") (pin "1") (pinfunction "1_1") (pintype "passive"))
      (node (ref "C163") (pin "1") (pinfunction "1_1") (pintype "passive"))
      (node (ref "C164") (pin "1") (pinfunction "1_1") (pintype "passive"))
      (node (ref "C17") (pin "1") (pinfunction "1_1") (pintype "passive"))
      (node (ref "C18") (pin "1") (pinfunction "1_1") (pintype "passive"))
      (node (ref "C19") (pin "1") (pinfunction "1_1") (pintype "passive"))
      (node (ref "C20") (pin "1") (pinfunction "1_1") (pintype "passive"))
      (node (ref "C21") (pin "1") (pinfunction "1_1") (pintype "passive"))
      (node (ref "C22") (pin "1") (pinfunction "1_1") (pintype "passive"))
      (node (ref "C25") (pin "1") (pinfunction "1_1") (pintype "passive"))
      (node (ref "C26") (pin "1") (pinfunction "1_1") (pintype "passive"))
      (node (ref "C27") (pin "1") (pinfunction "1_1") (pintype "passive"))
      (node (ref "C28") (pin "1") (pinfunction "1_1") (pintype "passive"))
      (node (ref "C29") (pin "1") (pinfunction "1_1") (pintype "passive"))
      (node (ref "C30") (pin "1") (pinfunction "1_1") (pintype "passive"))
      (node (ref "C31") (pin "1") (pinfunction "1_1") (pintype "passive"))
      (node (ref "C32") (pin "1") (pinfunction "1_1") (pintype "passive"))
      (node (ref "C33") (pin "1") (pinfunction "1_1") (pintype "passive"))
      (node (ref "C34") (pin "1") (pinfunction "1_1") (pintype "passive"))
      (node (ref "C35") (pin "1") (pinfunction "1_1") (pintype "passive"))
      (node (ref "C36") (pin "1") (pinfunction "1_1") (pintype "passive"))
      (node (ref "C37") (pin "1") (pinfunction "1_1") (pintype "passive"))
      (node (ref "C38") (pin "1") (pinfunction "1_1") (pintype "passive"))
      (node (ref "C39") (pin "1") (pinfunction "1_1") (pintype "passive"))
      (node (ref "C40") (pin "1") (pinfunction "1_1") (pintype "passive"))
      (node (ref "C41") (pin "1") (pinfunction "1_1") (pintype "passive"))
      (node (ref "C42") (pin "1") (pinfunction "1_1") (pintype "passive"))
      (node (ref "C43") (pin "1") (pinfunction "1_1") (pintype "passive"))
      (node (ref "C44") (pin "1") (pinfunction "1_1") (pintype "passive"))
      (node (ref "C45") (pin "1") (pinfunction "1_1") (pintype "passive"))
      (node (ref "C46") (pin "1") (pinfunction "1_1") (pintype "passive"))
      (node (ref "C47") (pin "1") (pinfunction "1_1") (pintype "passive"))
      (node (ref "C48") (pin "1") (pinfunction "1_1") (pintype "passive"))
      (node (ref "C49") (pin "1") (pinfunction "1_1") (pintype "passive"))
      (node (ref "C50") (pin "1") (pinfunction "1_1") (pintype "passive"))
      (node (ref "C55") (pin "2") (pinfunction "2_2") (pintype "passive"))
      (node (ref "C56") (pin "2") (pinfunction "2_2") (pintype "passive"))
      (node (ref "C57") (pin "2") (pinfunction "2_2") (pintype "passive"))
      (node (ref "C58") (pin "2") (pinfunction "2_2") (pintype "passive"))
      (node (ref "C59") (pin "1") (pinfunction "1_1") (pintype "passive"))
      (node (ref "C60") (pin "1") (pinfunction "1_1") (pintype "passive"))
      (node (ref "C61") (pin "1") (pinfunction "1_1") (pintype "passive"))
      (node (ref "C62") (pin "1") (pinfunction "1_1") (pintype "passive"))
      (node (ref "C63") (pin "1") (pinfunction "1_1") (pintype "passive"))
      (node (ref "C64") (pin "1") (pinfunction "1_1") (pintype "passive"))
      (node (ref "C67") (pin "1") (pinfunction "1_1") (pintype "passive"))
      (node (ref "C68") (pin "1") (pinfunction "1_1") (pintype "passive"))
      (node (ref "C69") (pin "1") (pinfunction "1_1") (pintype "passive"))
      (node (ref "C70") (pin "1") (pinfunction "1_1") (pintype "passive"))
      (node (ref "C71") (pin "1") (pinfunction "1_1") (pintype "passive"))
      (node (ref "C72") (pin "1") (pinfunction "1_1") (pintype "passive"))
      (node (ref "C73") (pin "1") (pinfunction "1_1") (pintype "passive"))
      (node (ref "C74") (pin "1") (pinfunction "1_1") (pintype "passive"))
      (node (ref "C75") (pin "1") (pinfunction "1_1") (pintype "passive"))
      (node (ref "C76") (pin "1") (pinfunction "1_1") (pintype "passive"))
      (node (ref "C77") (pin "1") (pinfunction "1_1") (pintype "passive"))
      (node (ref "C78") (pin "1") (pinfunction "1_1") (pintype "passive"))
      (node (ref "C79") (pin "1") (pinfunction "1_1") (pintype "passive"))
      (node (ref "C80") (pin "1") (pinfunction "1_1") (pintype "passive"))
      (node (ref "C81") (pin "1") (pinfunction "1_1") (pintype "passive"))
      (node (ref "C82") (pin "1") (pinfunction "1_1") (pintype "passive"))
      (node (ref "C83") (pin "1") (pinfunction "1_1") (pintype "passive"))
      (node (ref "C84") (pin "1") (pinfunction "1_1") (pintype "passive"))
      (node (ref "C85") (pin "1") (pinfunction "1_1") (pintype "passive"))
      (node (ref "C86") (pin "1") (pinfunction "1_1") (pintype "passive"))
      (node (ref "C87") (pin "1") (pinfunction "1_1") (pintype "passive"))
      (node (ref "C88") (pin "1") (pinfunction "1_1") (pintype "passive"))
      (node (ref "C89") (pin "1") (pinfunction "1_1") (pintype "passive"))
      (node (ref "C90") (pin "1") (pinfunction "1_1") (pintype "passive"))
      (node (ref "C91") (pin "1") (pinfunction "1_1") (pintype "passive"))
      (node (ref "C92") (pin "1") (pinfunction "1_1") (pintype "passive"))
      (node (ref "C97") (pin "2") (pinfunction "2_2") (pintype "passive"))
      (node (ref "C98") (pin "2") (pinfunction "2_2") (pintype "passive"))
      (node (ref "C99") (pin "2") (pinfunction "2_2") (pintype "passive"))
      (node (ref "R13") (pin "1") (pinfunction "1_1") (pintype "passive"))
      (node (ref "R14") (pin "1") (pinfunction "1_1") (pintype "passive"))
      (node (ref "R5") (pin "1") (pinfunction "1_1") (pintype "passive"))
      (node (ref "R6") (pin "1") (pinfunction "1_1") (pintype "passive"))
      (node (ref "U1") (pin "26") (pinfunction "NC_26") (pintype "passive"))
      (node (ref "U1") (pin "42") (pinfunction "MODE1_42") (pintype "passive"))
      (node (ref "U1") (pin "43") (pinfunction "GND_43") (pintype "passive"))
      (node (ref "U1") (pin "47") (pinfunction "NC_47") (pintype "passive"))
      (node (ref "U1") (pin "49") (pinfunction "EP_49") (pintype "passive"))
      (node (ref "U2") (pin "26") (pinfunction "NC_26") (pintype "passive"))
      (node (ref "U2") (pin "42") (pinfunction "MODE1_42") (pintype "passive"))
      (node (ref "U2") (pin "43") (pinfunction "GND_43") (pintype "passive"))
      (node (ref "U2") (pin "47") (pinfunction "NC_47") (pintype "passive"))
      (node (ref "U2") (pin "49") (pinfunction "EP_49") (pintype "passive"))
      (node (ref "U3") (pin "4") (pinfunction "GND_4") (pintype "passive"))
      (node (ref "U4") (pin "4") (pinfunction "GND_4") (pintype "passive"))
      (node (ref "U5") (pin "26") (pinfunction "NC_26") (pintype "passive"))
      (node (ref "U5") (pin "42") (pinfunction "MODE1_42") (pintype "passive"))
      (node (ref "U5") (pin "43") (pinfunction "GND_43") (pintype "passive"))
      (node (ref "U5") (pin "47") (pinfunction "NC_47") (pintype "passive"))
      (node (ref "U5") (pin "49") (pinfunction "EP_49") (pintype "passive"))
      (node (ref "U6") (pin "26") (pinfunction "NC_26") (pintype "passive"))
      (node (ref "U6") (pin "42") (pinfunction "MODE1_42") (pintype "passive"))
      (node (ref "U6") (pin "43") (pinfunction "GND_43") (pintype "passive"))
      (node (ref "U6") (pin "47") (pinfunction "NC_47") (pintype "passive"))
      (node (ref "U6") (pin "49") (pinfunction "EP_49") (pintype "passive"))
      (node (ref "U7") (pin "4") (pinfunction "GND_4") (pintype "passive"))
      (node (ref "U8") (pin "4") (pinfunction "GND_4") (pintype "passive"))
      (node (ref "Y1") (pin "2") (pinfunction "GND_2") (pintype "passive"))
      (node (ref "Y1") (pin "4") (pinfunction "GND_4") (pintype "passive"))
      (node (ref "Y2") (pin "2") (pinfunction "GND_2") (pintype "passive"))
      (node (ref "Y2") (pin "4") (pinfunction "GND_4") (pintype "passive"))
      (node (ref "Y3") (pin "2") (pinfunction "GND_2") (pintype "passive"))
      (node (ref "Y3") (pin "4") (pinfunction "GND_4") (pintype "passive"))
      (node (ref "Y4") (pin "2") (pinfunction "GND_2") (pintype "passive"))
      (node (ref "Y4") (pin "4") (pinfunction "GND_4") (pintype "passive"))
    )
    (net (code "90") (name "Net-(U1-RST#)") (class "Default")
      (node (ref "C17") (pin "2") (pinfunction "2_2") (pintype "passive"))
      (node (ref "R1") (pin "2") (pinfunction "2_2") (pintype "passive"))
      (node (ref "U1") (pin "38") (pinfunction "RST#_38") (pintype "passive"))
    )
    (net (code "91") (name "Net-(U1-TEXT)") (class "Default")
      (node (ref "R7") (pin "2") (pinfunction "2_2") (pintype "passive"))
      (node (ref "U1") (pin "36") (pinfunction "TEXT_36") (pintype "passive"))
    )
    (net (code "92") (name "Net-(U1-TME)") (class "Default")
      (node (ref "C23") (pin "1") (pinfunction "1_1") (pintype "passive"))
      (node (ref "R5") (pin "2") (pinfunction "2_2") (pintype "passive"))
      (node (ref "U1") (pin "1") (pinfunction "TME_1") (pintype "passive"))
    )
    (net (code "93") (name "Net-(U1-UAO{slash}GPIO8)") (class "Default")
      (node (ref "R3") (pin "2") (pinfunction "2_2") (pintype "passive"))
      (node (ref "U1") (pin "37") (pinfunction "UAO/GPIO8_37") (pintype "passive"))
    )
    (net (code "94") (name "Net-(U2-RST#)") (class "Default")
      (node (ref "C18") (pin "2") (pinfunction "2_2") (pintype "passive"))
      (node (ref "R2") (pin "2") (pinfunction "2_2") (pintype "passive"))
      (node (ref "U2") (pin "38") (pinfunction "RST#_38") (pintype "passive"))
    )
    (net (code "95") (name "Net-(U2-TEXT)") (class "Default")
      (node (ref "R8") (pin "2") (pinfunction "2_2") (pintype "passive"))
      (node (ref "U2") (pin "36") (pinfunction "TEXT_36") (pintype "passive"))
    )
    (net (code "96") (name "Net-(U2-TME)") (class "Default")
      (node (ref "C24") (pin "1") (pinfunction "1_1") (pintype "passive"))
      (node (ref "R6") (pin "2") (pinfunction "2_2") (pintype "passive"))
      (node (ref "U2") (pin "1") (pinfunction "TME_1") (pintype "passive"))
    )
    (net (code "97") (name "Net-(U2-UAO{slash}GPIO8)") (class "Default")
      (node (ref "R4") (pin "2") (pinfunction "2_2") (pintype "passive"))
      (node (ref "U2") (pin "37") (pinfunction "UAO/GPIO8_37") (pintype "passive"))
    )
    (net (code "98") (name "Net-(U5-RST#)") (class "Default")
      (node (ref "C59") (pin "2") (pinfunction "2_2") (pintype "passive"))
      (node (ref "R9") (pin "2") (pinfunction "2_2") (pintype "passive"))
      (node (ref "U5") (pin "38") (pinfunction "RST#_38") (pintype "passive"))
    )
    (net (code "99") (name "Net-(U5-TEXT)") (class "Default")
      (node (ref "R15") (pin "2") (pinfunction "2_2") (pintype "passive"))
      (node (ref "U5") (pin "36") (pinfunction "TEXT_36") (pintype "passive"))
    )
    (net (code "100") (name "Net-(U5-TME)") (class "Default")
      (node (ref "C65") (pin "1") (pinfunction "1_1") (pintype "passive"))
      (node (ref "R13") (pin "2") (pinfunction "2_2") (pintype "passive"))
      (node (ref "U5") (pin "1") (pinfunction "TME_1") (pintype "passive"))
    )
    (net (code "101") (name "Net-(U5-UAO{slash}GPIO8)") (class "Default")
      (node (ref "R11") (pin "2") (pinfunction "2_2") (pintype "passive"))
      (node (ref "U5") (pin "37") (pinfunction "UAO/GPIO8_37") (pintype "passive"))
    )
    (net (code "102") (name "Net-(U6-RST#)") (class "Default")
      (node (ref "C60") (pin "2") (pinfunction "2_2") (pintype "passive"))
      (node (ref "R10") (pin "2") (pinfunction "2_2") (pintype "passive"))
      (node (ref "U6") (pin "38") (pinfunction "RST#_38") (pintype "passive"))
    )
    (net (code "103") (name "Net-(U6-TEXT)") (class "Default")
      (node (ref "R16") (pin "2") (pinfunction "2_2") (pintype "passive"))
      (node (ref "U6") (pin "36") (pinfunction "TEXT_36") (pintype "passive"))
    )
    (net (code "104") (name "Net-(U6-TME)") (class "Default")
      (node (ref "C66") (pin "1") (pinfunction "1_1") (pintype "passive"))
      (node (ref "R14") (pin "2") (pinfunction "2_2") (pintype "passive"))
      (node (ref "U6") (pin "1") (pinfunction "TME_1") (pintype "passive"))
    )
    (net (code "105") (name "Net-(U6-UAO{slash}GPIO8)") (class "Default")
      (node (ref "R12") (pin "2") (pinfunction "2_2") (pintype "passive"))
      (node (ref "U6") (pin "37") (pinfunction "UAO/GPIO8_37") (pintype "passive"))
    )
    (net (code "106") (name "VBUS") (class "Default")
      (node (ref "C41") (pin "2") (pinfunction "2_2") (pintype "passive"))
      (node (ref "C42") (pin "2") (pinfunction "2_2") (pintype "passive"))
      (node (ref "C46") (pin "2") (pinfunction "2_2") (pintype "passive"))
      (node (ref "C47") (pin "2") (pinfunction "2_2") (pintype "passive"))
      (node (ref "C83") (pin "2") (pinfunction "2_2") (pintype "passive"))
      (node (ref "C84") (pin "2") (pinfunction "2_2") (pintype "passive"))
      (node (ref "C88") (pin "2") (pinfunction "2_2") (pintype "passive"))
      (node (ref "C89") (pin "2") (pinfunction "2_2") (pintype "passive"))
      (node (ref "U1") (pin "12") (pinfunction "VBUS_12") (pintype "passive"))
      (node (ref "U1") (pin "45") (pinfunction "VREG_IN_45") (pintype "passive"))
      (node (ref "U2") (pin "12") (pinfunction "VBUS_12") (pintype "passive"))
      (node (ref "U2") (pin "45") (pinfunction "VREG_IN_45") (pintype "passive"))
      (node (ref "U5") (pin "12") (pinfunction "VBUS_12") (pintype "passive"))
      (node (ref "U5") (pin "45") (pinfunction "VREG_IN_45") (pintype "passive"))
      (node (ref "U6") (pin "12") (pinfunction "VBUS_12") (pintype "passive"))
      (node (ref "U6") (pin "45") (pinfunction "VREG_IN_45") (pintype "passive"))
    )
    (net (code "107") (name "VCC1V2-A") (class "Default")
      (node (ref "C19") (pin "2") (pinfunction "2_2") (pintype "passive"))
      (node (ref "C20") (pin "2") (pinfunction "2_2") (pintype "passive"))
      (node (ref "C25") (pin "2") (pinfunction "2_2") (pintype "passive"))
      (node (ref "C26") (pin "2") (pinfunction "2_2") (pintype "passive"))
      (node (ref "C27") (pin "2") (pinfunction "2_2") (pintype "passive"))
      (node (ref "C28") (pin "2") (pinfunction "2_2") (pintype "passive"))
      (node (ref "C29") (pin "2") (pinfunction "2_2") (pintype "passive"))
      (node (ref "C30") (pin "2") (pinfunction "2_2") (pintype "passive"))
      (node (ref "C31") (pin "2") (pinfunction "2_2") (pintype "passive"))
      (node (ref "C32") (pin "2") (pinfunction "2_2") (pintype "passive"))
      (node (ref "L1") (pin "2") (pinfunction "2_2") (pintype "passive"))
      (node (ref "U1") (pin "10") (pinfunction "VCC12_10") (pintype "passive"))
      (node (ref "U1") (pin "18") (pinfunction "VCC12_18") (pintype "passive"))
      (node (ref "U1") (pin "21") (pinfunction "VCC12_21") (pintype "passive"))
      (node (ref "U1") (pin "24") (pinfunction "VCC12_24") (pintype "passive"))
      (node (ref "U1") (pin "29") (pinfunction "VCC12_29") (pintype "passive"))
      (node (ref "U1") (pin "32") (pinfunction "VCC12_32") (pintype "passive"))
      (node (ref "U1") (pin "4") (pinfunction "VCC12_4") (pintype "passive"))
      (node (ref "U1") (pin "40") (pinfunction "VCC12_40") (pintype "passive"))
    )
    (net (code "108") (name "VCC1V2-B") (class "Default")
      (node (ref "C21") (pin "2") (pinfunction "2_2") (pintype "passive"))
      (node (ref "C22") (pin "2") (pinfunction "2_2") (pintype "passive"))
      (node (ref "C33") (pin "2") (pinfunction "2_2") (pintype "passive"))
      (node (ref "C34") (pin "2") (pinfunction "2_2") (pintype "passive"))
      (node (ref "C35") (pin "2") (pinfunction "2_2") (pintype "passive"))
      (node (ref "C36") (pin "2") (pinfunction "2_2") (pintype "passive"))
      (node (ref "C37") (pin "2") (pinfunction "2_2") (pintype "passive"))
      (node (ref "C38") (pin "2") (pinfunction "2_2") (pintype "passive"))
      (node (ref "C39") (pin "2") (pinfunction "2_2") (pintype "passive"))
      (node (ref "C40") (pin "2") (pinfunction "2_2") (pintype "passive"))
      (node (ref "L2") (pin "2") (pinfunction "2_2") (pintype "passive"))
      (node (ref "U2") (pin "10") (pinfunction "VCC12_10") (pintype "passive"))
      (node (ref "U2") (pin "18") (pinfunction "VCC12_18") (pintype "passive"))
      (node (ref "U2") (pin "21") (pinfunction "VCC12_21") (pintype "passive"))
      (node (ref "U2") (pin "24") (pinfunction "VCC12_24") (pintype "passive"))
      (node (ref "U2") (pin "29") (pinfunction "VCC12_29") (pintype "passive"))
      (node (ref "U2") (pin "32") (pinfunction "VCC12_32") (pintype "passive"))
      (node (ref "U2") (pin "4") (pinfunction "VCC12_4") (pintype "passive"))
      (node (ref "U2") (pin "40") (pinfunction "VCC12_40") (pintype "passive"))
    )
    (net (code "109") (name "VCC1V2-C") (class "Default")
      (node (ref "C61") (pin "2") (pinfunction "2_2") (pintype "passive"))
      (node (ref "C62") (pin "2") (pinfunction "2_2") (pintype "passive"))
      (node (ref "C67") (pin "2") (pinfunction "2_2") (pintype "passive"))
      (node (ref "C68") (pin "2") (pinfunction "2_2") (pintype "passive"))
      (node (ref "C69") (pin "2") (pinfunction "2_2") (pintype "passive"))
      (node (ref "C70") (pin "2") (pinfunction "2_2") (pintype "passive"))
      (node (ref "C71") (pin "2") (pinfunction "2_2") (pintype "passive"))
      (node (ref "C72") (pin "2") (pinfunction "2_2") (pintype "passive"))
      (node (ref "C73") (pin "2") (pinfunction "2_2") (pintype "passive"))
      (node (ref "C74") (pin "2") (pinfunction "2_2") (pintype "passive"))
      (node (ref "L3") (pin "2") (pinfunction "2_2") (pintype "passive"))
      (node (ref "U5") (pin "10") (pinfunction "VCC12_10") (pintype "passive"))
      (node (ref "U5") (pin "18") (pinfunction "VCC12_18") (pintype "passive"))
      (node (ref "U5") (pin "21") (pinfunction "VCC12_21") (pintype "passive"))
      (node (ref "U5") (pin "24") (pinfunction "VCC12_24") (pintype "passive"))
      (node (ref "U5") (pin "29") (pinfunction "VCC12_29") (pintype "passive"))
      (node (ref "U5") (pin "32") (pinfunction "VCC12_32") (pintype "passive"))
      (node (ref "U5") (pin "4") (pinfunction "VCC12_4") (pintype "passive"))
      (node (ref "U5") (pin "40") (pinfunction "VCC12_40") (pintype "passive"))
    )
    (net (code "110") (name "VCC1V2-D") (class "Default")
      (node (ref "C63") (pin "2") (pinfunction "2_2") (pintype "passive"))
      (node (ref "C64") (pin "2") (pinfunction "2_2") (pintype "passive"))
      (node (ref "C75") (pin "2") (pinfunction "2_2") (pintype "passive"))
      (node (ref "C76") (pin "2") (pinfunction "2_2") (pintype "passive"))
      (node (ref "C77") (pin "2") (pinfunction "2_2") (pintype "passive"))
      (node (ref "C78") (pin "2") (pinfunction "2_2") (pintype "passive"))
      (node (ref "C79") (pin "2") (pinfunction "2_2") (pintype "passive"))
      (node (ref "C80") (pin "2") (pinfunction "2_2") (pintype "passive"))
      (node (ref "C81") (pin "2") (pinfunction "2_2") (pintype "passive"))
      (node (ref "C82") (pin "2") (pinfunction "2_2") (pintype "passive"))
      (node (ref "L4") (pin "2") (pinfunction "2_2") (pintype "passive"))
      (node (ref "U6") (pin "10") (pinfunction "VCC12_10") (pintype "passive"))
      (node (ref "U6") (pin "18") (pinfunction "VCC12_18") (pintype "passive"))
      (node (ref "U6") (pin "21") (pinfunction "VCC12_21") (pintype "passive"))
      (node (ref "U6") (pin "24") (pinfunction "VCC12_24") (pintype "passive"))
      (node (ref "U6") (pin "29") (pinfunction "VCC12_29") (pintype "passive"))
      (node (ref "U6") (pin "32") (pinfunction "VCC12_32") (pintype "passive"))
      (node (ref "U6") (pin "4") (pinfunction "VCC12_4") (pintype "passive"))
      (node (ref "U6") (pin "40") (pinfunction "VCC12_40") (pintype "passive"))
    )
    (net (code "111") (name "VCC3V3-A") (class "Default")
      (node (ref "C161") (pin "2") (pinfunction "2_2") (pintype "passive"))
      (node (ref "C23") (pin "2") (pinfunction "2_2") (pintype "passive"))
      (node (ref "C43") (pin "2") (pinfunction "2_2") (pintype "passive"))
      (node (ref "C44") (pin "2") (pinfunction "2_2") (pintype "passive"))
      (node (ref "C45") (pin "2") (pinfunction "2_2") (pintype "passive"))
      (node (ref "R1") (pin "1") (pinfunction "1_1") (pintype "passive"))
      (node (ref "R3") (pin "1") (pinfunction "1_1") (pintype "passive"))
      (node (ref "R7") (pin "1") (pinfunction "1_1") (pintype "passive"))
      (node (ref "U1") (pin "14") (pinfunction "VCC33_14") (pintype "passive"))
      (node (ref "U1") (pin "39") (pinfunction "VCC33_39") (pintype "passive"))
      (node (ref "U1") (pin "46") (pinfunction "MODE0_46") (pintype "passive"))
      (node (ref "U1") (pin "7") (pinfunction "VCC33_7") (pintype "passive"))
      (node (ref "U3") (pin "3") (pinfunction "WP#_3") (pintype "passive"))
      (node (ref "U3") (pin "7") (pinfunction "HOLD#_7") (pintype "passive"))
      (node (ref "U3") (pin "8") (pinfunction "VCC_8") (pintype "passive"))
    )
    (net (code "112") (name "VCC3V3-B") (class "Default")
      (node (ref "C162") (pin "2") (pinfunction "2_2") (pintype "passive"))
      (node (ref "C24") (pin "2") (pinfunction "2_2") (pintype "passive"))
      (node (ref "C48") (pin "2") (pinfunction "2_2") (pintype "passive"))
      (node (ref "C49") (pin "2") (pinfunction "2_2") (pintype "passive"))
      (node (ref "C50") (pin "2") (pinfunction "2_2") (pintype "passive"))
      (node (ref "R2") (pin "1") (pinfunction "1_1") (pintype "passive"))
      (node (ref "R4") (pin "1") (pinfunction "1_1") (pintype "passive"))
      (node (ref "R8") (pin "1") (pinfunction "1_1") (pintype "passive"))
      (node (ref "U2") (pin "14") (pinfunction "VCC33_14") (pintype "passive"))
      (node (ref "U2") (pin "39") (pinfunction "VCC33_39") (pintype "passive"))
      (node (ref "U2") (pin "46") (pinfunction "MODE0_46") (pintype "passive"))
      (node (ref "U2") (pin "7") (pinfunction "VCC33_7") (pintype "passive"))
      (node (ref "U4") (pin "3") (pinfunction "WP#_3") (pintype "passive"))
      (node (ref "U4") (pin "7") (pinfunction "HOLD#_7") (pintype "passive"))
      (node (ref "U4") (pin "8") (pinfunction "VCC_8") (pintype "passive"))
    )
    (net (code "113") (name "VCC3V3-C") (class "Default")
      (node (ref "C163") (pin "2") (pinfunction "2_2") (pintype "passive"))
      (node (ref "C65") (pin "2") (pinfunction "2_2") (pintype "passive"))
      (node (ref "C85") (pin "2") (pinfunction "2_2") (pintype "passive"))
      (node (ref "C86") (pin "2") (pinfunction "2_2") (pintype "passive"))
      (node (ref "C87") (pin "2") (pinfunction "2_2") (pintype "passive"))
      (node (ref "R11") (pin "1") (pinfunction "1_1") (pintype "passive"))
      (node (ref "R15") (pin "1") (pinfunction "1_1") (pintype "passive"))
      (node (ref "R9") (pin "1") (pinfunction "1_1") (pintype "passive"))
      (node (ref "U5") (pin "14") (pinfunction "VCC33_14") (pintype "passive"))
      (node (ref "U5") (pin "39") (pinfunction "VCC33_39") (pintype "passive"))
      (node (ref "U5") (pin "46") (pinfunction "MODE0_46") (pintype "passive"))
      (node (ref "U5") (pin "7") (pinfunction "VCC33_7") (pintype "passive"))
      (node (ref "U7") (pin "3") (pinfunction "WP#_3") (pintype "passive"))
      (node (ref "U7") (pin "7") (pinfunction "HOLD#_7") (pintype "passive"))
      (node (ref "U7") (pin "8") (pinfunction "VCC_8") (pintype "passive"))
    )
    (net (code "114") (name "VCC3V3-D") (class "Default")
      (node (ref "C164") (pin "2") (pinfunction "2_2") (pintype "passive"))
      (node (ref "C66") (pin "2") (pinfunction "2_2") (pintype "passive"))
      (node (ref "C90") (pin "2") (pinfunction "2_2") (pintype "passive"))
      (node (ref "C91") (pin "2") (pinfunction "2_2") (pintype "passive"))
      (node (ref "C92") (pin "2") (pinfunction "2_2") (pintype "passive"))
      (node (ref "R10") (pin "1") (pinfunction "1_1") (pintype "passive"))
      (node (ref "R12") (pin "1") (pinfunction "1_1") (pintype "passive"))
      (node (ref "R16") (pin "1") (pinfunction "1_1") (pintype "passive"))
      (node (ref "U6") (pin "14") (pinfunction "VCC33_14") (pintype "passive"))
      (node (ref "U6") (pin "39") (pinfunction "VCC33_39") (pintype "passive"))
      (node (ref "U6") (pin "46") (pinfunction "MODE0_46") (pintype "passive"))
      (node (ref "U6") (pin "7") (pinfunction "VCC33_7") (pintype "passive"))
      (node (ref "U8") (pin "3") (pinfunction "WP#_3") (pintype "passive"))
      (node (ref "U8") (pin "7") (pinfunction "HOLD#_7") (pintype "passive"))
      (node (ref "U8") (pin "8") (pinfunction "VCC_8") (pintype "passive"))
    )
    (net (code "115") (name "unconnected-(U1-GPIO7-Pad41)") (class "Default")
      (node (ref "U1") (pin "41") (pinfunction "GPIO7_41") (pintype "passive+no_connect"))
    )
    (net (code "116") (name "unconnected-(U1-GPIO9-Pad48)") (class "Default")
      (node (ref "U1") (pin "48") (pinfunction "GPIO9_48") (pintype "passive+no_connect"))
    )
    (net (code "117") (name "unconnected-(U1-NC-Pad16)") (class "Default")
      (node (ref "U1") (pin "16") (pinfunction "NC_16") (pintype "passive+no_connect"))
    )
    (net (code "118") (name "unconnected-(U1-NC-Pad17)") (class "Default")
      (node (ref "U1") (pin "17") (pinfunction "NC_17") (pintype "passive+no_connect"))
    )
    (net (code "119") (name "unconnected-(U1-NC-Pad25)") (class "Default")
      (node (ref "U1") (pin "25") (pinfunction "NC_25") (pintype "passive+no_connect"))
    )
    (net (code "120") (name "unconnected-(U1-NC-Pad35)") (class "Default")
      (node (ref "U1") (pin "35") (pinfunction "NC_35") (pintype "passive+no_connect"))
    )
    (net (code "121") (name "unconnected-(U2-GPIO7-Pad41)") (class "Default")
      (node (ref "U2") (pin "41") (pinfunction "GPIO7_41") (pintype "passive+no_connect"))
    )
    (net (code "122") (name "unconnected-(U2-GPIO9-Pad48)") (class "Default")
      (node (ref "U2") (pin "48") (pinfunction "GPIO9_48") (pintype "passive+no_connect"))
    )
    (net (code "123") (name "unconnected-(U2-NC-Pad16)") (class "Default")
      (node (ref "U2") (pin "16") (pinfunction "NC_16") (pintype "passive+no_connect"))
    )
    (net (code "124") (name "unconnected-(U2-NC-Pad17)") (class "Default")
      (node (ref "U2") (pin "17") (pinfunction "NC_17") (pintype "passive+no_connect"))
    )
    (net (code "125") (name "unconnected-(U2-NC-Pad25)") (class "Default")
      (node (ref "U2") (pin "25") (pinfunction "NC_25") (pintype "passive+no_connect"))
    )
    (net (code "126") (name "unconnected-(U2-NC-Pad35)") (class "Default")
      (node (ref "U2") (pin "35") (pinfunction "NC_35") (pintype "passive+no_connect"))
    )
    (net (code "127") (name "unconnected-(U5-GPIO7-Pad41)") (class "Default")
      (node (ref "U5") (pin "41") (pinfunction "GPIO7_41") (pintype "passive+no_connect"))
    )
    (net (code "128") (name "unconnected-(U5-GPIO9-Pad48)") (class "Default")
      (node (ref "U5") (pin "48") (pinfunction "GPIO9_48") (pintype "passive+no_connect"))
    )
    (net (code "129") (name "unconnected-(U5-NC-Pad16)") (class "Default")
      (node (ref "U5") (pin "16") (pinfunction "NC_16") (pintype "passive+no_connect"))
    )
    (net (code "130") (name "unconnected-(U5-NC-Pad17)") (class "Default")
      (node (ref "U5") (pin "17") (pinfunction "NC_17") (pintype "passive+no_connect"))
    )
    (net (code "131") (name "unconnected-(U5-NC-Pad25)") (class "Default")
      (node (ref "U5") (pin "25") (pinfunction "NC_25") (pintype "passive+no_connect"))
    )
    (net (code "132") (name "unconnected-(U5-NC-Pad35)") (class "Default")
      (node (ref "U5") (pin "35") (pinfunction "NC_35") (pintype "passive+no_connect"))
    )
    (net (code "133") (name "unconnected-(U6-GPIO7-Pad41)") (class "Default")
      (node (ref "U6") (pin "41") (pinfunction "GPIO7_41") (pintype "passive+no_connect"))
    )
    (net (code "134") (name "unconnected-(U6-GPIO9-Pad48)") (class "Default")
      (node (ref "U6") (pin "48") (pinfunction "GPIO9_48") (pintype "passive+no_connect"))
    )
    (net (code "135") (name "unconnected-(U6-NC-Pad16)") (class "Default")
      (node (ref "U6") (pin "16") (pinfunction "NC_16") (pintype "passive+no_connect"))
    )
    (net (code "136") (name "unconnected-(U6-NC-Pad17)") (class "Default")
      (node (ref "U6") (pin "17") (pinfunction "NC_17") (pintype "passive+no_connect"))
    )
    (net (code "137") (name "unconnected-(U6-NC-Pad25)") (class "Default")
      (node (ref "U6") (pin "25") (pinfunction "NC_25") (pintype "passive+no_connect"))
    )
    (net (code "138") (name "unconnected-(U6-NC-Pad35)") (class "Default")
      (node (ref "U6") (pin "35") (pinfunction "NC_35") (pintype "passive+no_connect"))
    )
  )
)
